# OpenPLCv0_2_0_Buzzer.net
KiCad netlist of a schematic drawn in Altium Designer
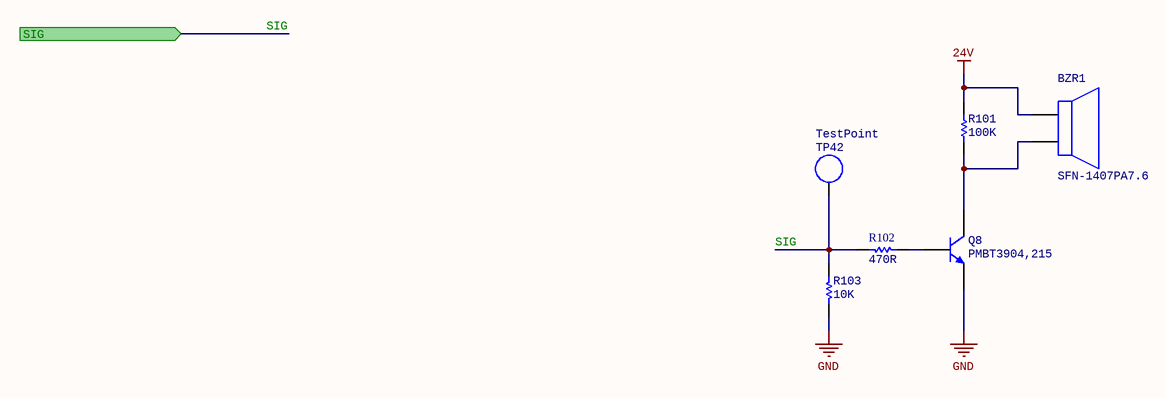
[diagram p0: OpenPLCv0.2.0_Buzzer.SchDoc]

(export (version "E")
  (design (tool "Eeschema 10.0.6"))
  (components
    (comp (ref "BZR1")
      (value "SFN-1407PA7.6")
      (footprint "SFN-1407PA7.6")
      (description "Piezo YES 3300±500Hz 85dB @ 24V, 10cm 24V Φ23.5mm Through Hole Buzzers RoHS")
      (libsource (lib "BrauV2_Misc") (part "SFN-1407PA7.6"))
    )
    (comp (ref "Q8")
      (value "PMBT3904,215")
      (footprint "SOT23-3")
      (description "NPN 200mA 40V 250mW SOT-23(SOT-23-3) Transistors (NPN/PNP) RoHS")
      (libsource (lib "BrauV2_Transistor") (part "PMBT3904,215"))
    )
    (comp (ref "R101")
      (value "RC0402FR-07100KL")
      (footprint "SMD_RES_0402(1005)_N")
      (description "100kΩ ±1% 1/16W ±100ppm/℃ 0402 Chip Resistor - Surface Mount RoHS")
      (fields (field (name "TOLERANCE") "1%") (field (name "RESISTANCE") "100K"))
      (libsource (lib "BrauV2_Resistor") (part "100K 0402 1% 1/16W"))
    )
    (comp (ref "R102")
      (value "RC0402FR-07470RL")
      (footprint "SMD_RES_0402(1005)_N")
      (description "470Ω ±1% 1/16W ±100ppm/℃ 0402 Chip Resistor - Surface Mount RoHS")
      (fields (field (name "TOLERANCE") "1%") (field (name "RESISTANCE") "470R"))
      (libsource (lib "BrauV2_Resistor") (part "470R 0402 1% 1W"))
    )
    (comp (ref "R103")
      (value "RC0402FR-0710KL")
      (footprint "SMD_RES_0402(1005)_N")
      (description "10kΩ ±1% 1/16W ±100ppm/℃ 0402 Chip Resistor - Surface Mount RoHS")
      (fields (field (name "TOLERANCE") "1%") (field (name "RESISTANCE") "10K"))
      (libsource (lib "BrauV2_Resistor") (part "10K 0402 1% 1/16W"))
    )
    (comp (ref "TP42")
      (value "TestPoint")
      (footprint "Pad")
      (libsource (lib "OpenPLCv0.2.0_Misc") (part "Test point"))
    )
  )
  (nets
    (net (code "1") (name "/SIG") (class "Default")
      (node (ref "R102") (pin "1") (pinfunction "1_1") (pintype "passive"))
      (node (ref "R103") (pin "2") (pinfunction "2_2") (pintype "passive"))
      (node (ref "TP42") (pin "1") (pinfunction "1_1") (pintype "passive"))
    )
    (net (code "2") (name "24V") (class "Default")
      (node (ref "BZR1") (pin "1") (pinfunction "1_1") (pintype "passive"))
      (node (ref "R101") (pin "2") (pinfunction "2_2") (pintype "passive"))
    )
    (net (code "3") (name "GND") (class "Default")
      (node (ref "Q8") (pin "2") (pinfunction "E_2") (pintype "passive"))
      (node (ref "R103") (pin "1") (pinfunction "1_1") (pintype "passive"))
    )
    (net (code "4") (name "Net-(Q8-B)") (class "Default")
      (node (ref "Q8") (pin "1") (pinfunction "B_1") (pintype "passive"))
      (node (ref "R102") (pin "2") (pinfunction "2_2") (pintype "passive"))
    )
    (net (code "5") (name "Net-(Q8-C)") (class "Default")
      (node (ref "BZR1") (pin "2") (pinfunction "2_2") (pintype "passive"))
      (node (ref "Q8") (pin "3") (pinfunction "C_3") (pintype "passive"))
      (node (ref "R101") (pin "1") (pinfunction "1_1") (pintype "passive"))
    )
  )
)
